# quadcopter.net
KiCad netlist of a schematic drawn in EAGLE
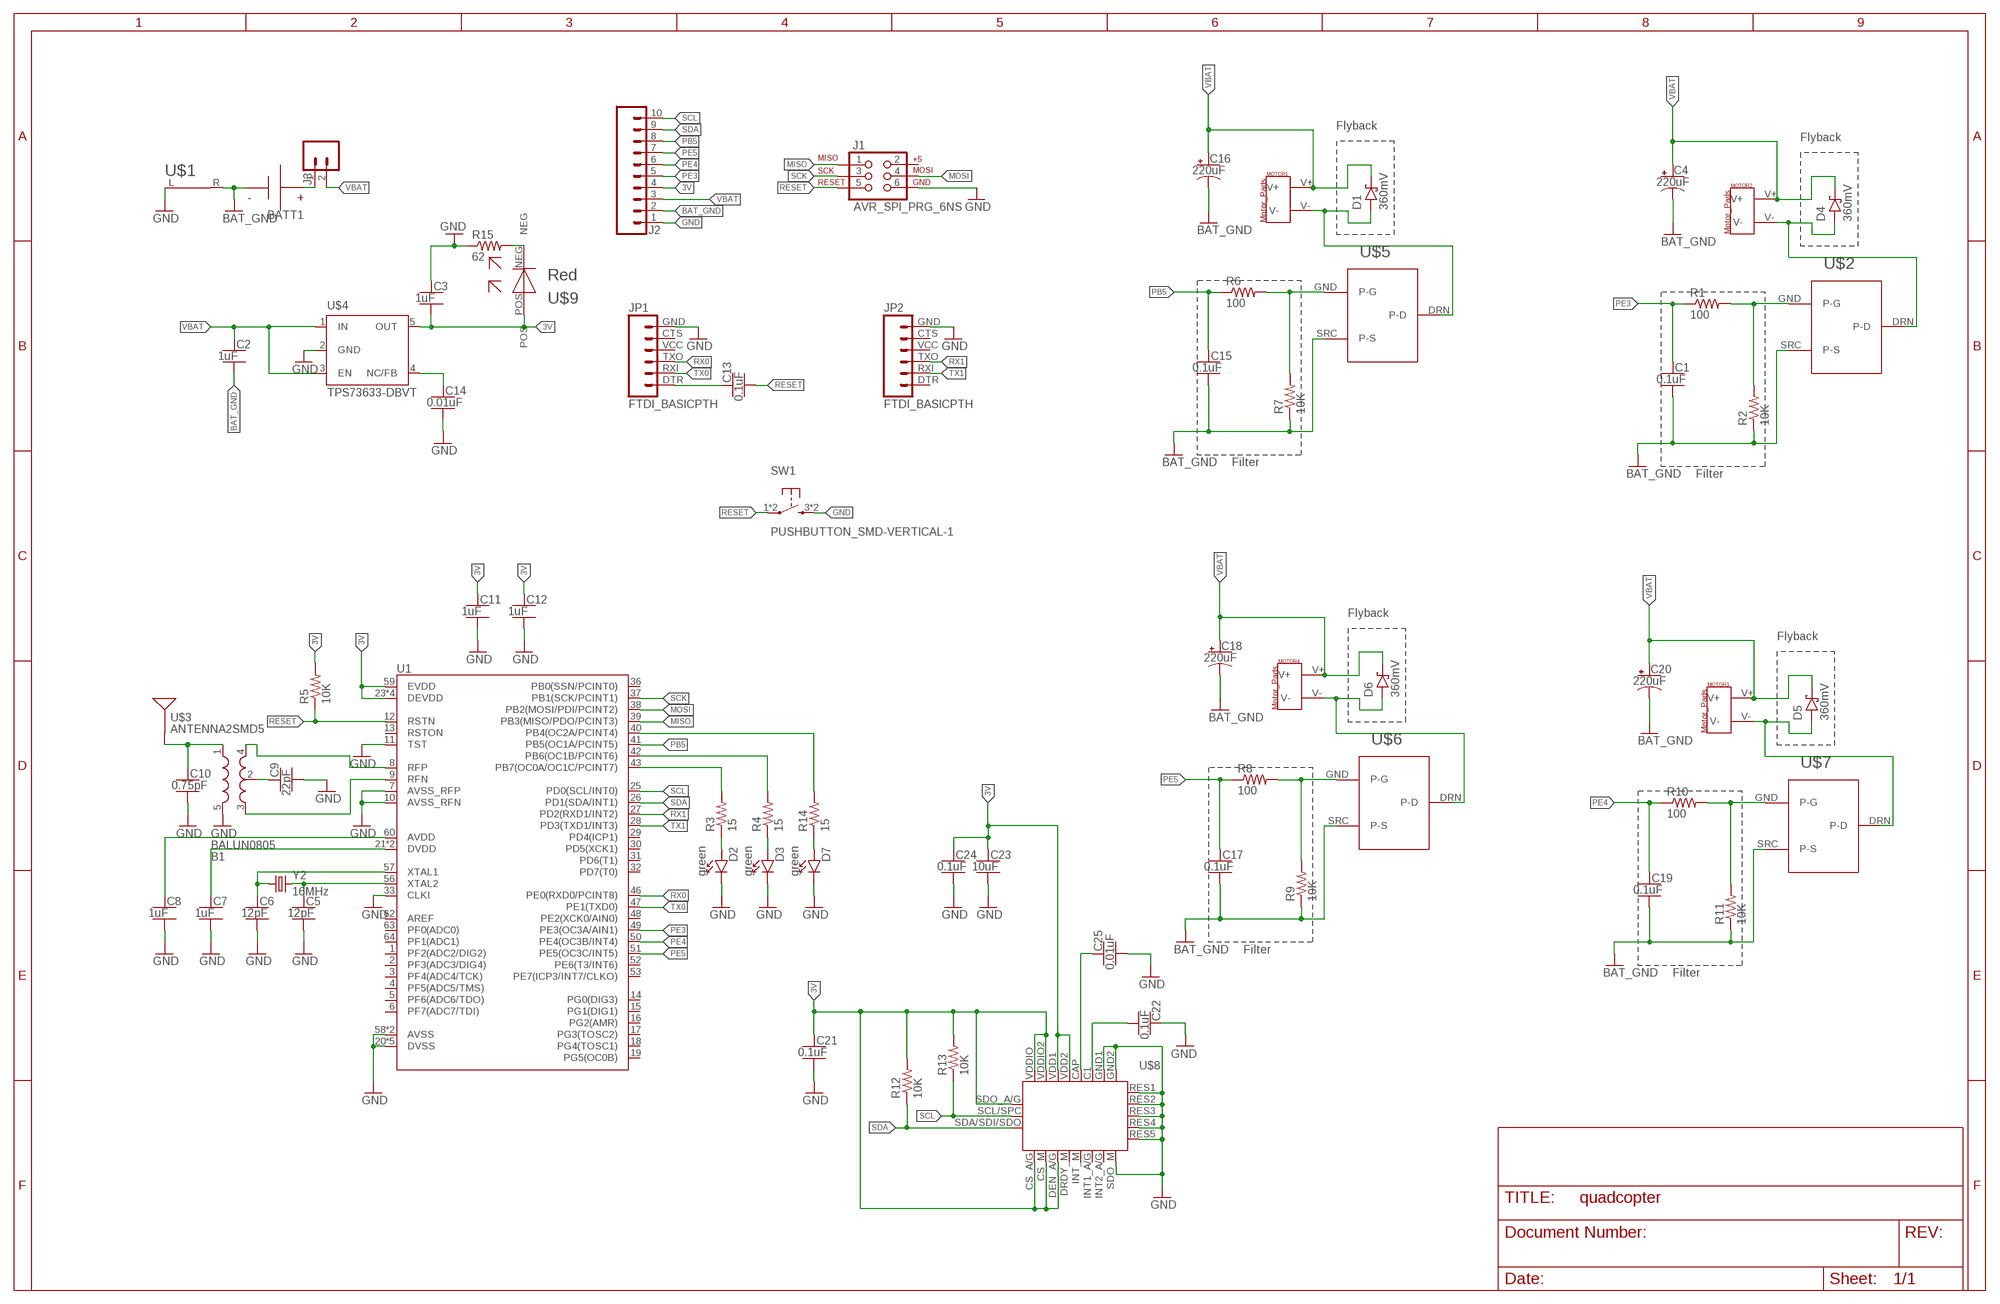
[diagram p0: schematic, sheet 1]

(export (version "E")
  (design (tool "Eeschema 10.0.6"))
  (components
    (comp (ref "B1")
      (value "BALUN0805")
      (footprint "eagle-import:BALUN")
      (fields (field (name "MFR") "Wurth Electronics Inc") (field (name "MPN") "748421245"))
      (libsource (lib "eagle-import") (part "BALUN0805"))
    )
    (comp (ref "BATT1")
      (value "BATTERY-HUBSAN-W/HOLDER")
      (footprint "eagle-import:BATTERY-W_HOLDER-380MAH-HUBSAN")
      (fields
        (field (name "MFR") "HUBSAN")
        (field (name "MPN") "X4-H107C-8-in-1")
        (field (name "CREATOR") "Swanson")
      )
      (libsource (lib "eagle-import") (part "BATTERY-HUBSAN-W/HOLDER"))
    )
    (comp (ref "C1")
      (value "0.1uF")
      (footprint "eagle-import:CAPC2012X140_HS")
      (fields
        (field (name "MFR") "Murata Electronics North America")
        (field (name "MPN") "GRM21BR71H104KA01L")
      )
      (libsource (lib "eagle-import") (part "CAPACITOR-NP_SMD-2012-0805_CERAMIC-0.1UF"))
    )
    (comp (ref "C2")
      (value "1uF")
      (footprint "eagle-import:CAPC2012X140_HS")
      (fields
        (field (name "MFR") "Murata Electronics North America")
        (field (name "MPN") "GRM21BR71H105KA12L")
      )
      (libsource (lib "eagle-import") (part "CAPACITOR-NP_SMD-2012-0805_CERAMIC-1UF"))
    )
    (comp (ref "C3")
      (value "1uF")
      (footprint "eagle-import:CAPC2012X140_HS")
      (fields
        (field (name "MFR") "Murata Electronics North America")
        (field (name "MPN") "GRM21BR71H105KA12L")
      )
      (libsource (lib "eagle-import") (part "CAPACITOR-NP_SMD-2012-0805_CERAMIC-1UF"))
    )
    (comp (ref "C4")
      (value "220uF")
      (footprint "eagle-import:CAPMP7343X310_HS")
      (fields (field (name "MFR") "AVX Corporation") (field (name "MPN") "TAJD227K006RNJ"))
      (libsource (lib "eagle-import") (part "CAPACITOR-POL_SMD-7043-D_TANTALUM-220UF"))
    )
    (comp (ref "C5")
      (value "12pF")
      (footprint "eagle-import:CAPC2012X140_HS")
      (fields
        (field (name "MFR") "Murata Electronics North America")
        (field (name "MPN") "GRM21A5C2E120JW01D")
      )
      (libsource (lib "eagle-import") (part "CAPACITOR-NP_SMD-2012-0805_CERAMIC-12PF"))
    )
    (comp (ref "C6")
      (value "12pF")
      (footprint "eagle-import:CAPC2012X140_HS")
      (fields
        (field (name "MFR") "Murata Electronics North America")
        (field (name "MPN") "GRM21A5C2E120JW01D")
      )
      (libsource (lib "eagle-import") (part "CAPACITOR-NP_SMD-2012-0805_CERAMIC-12PF"))
    )
    (comp (ref "C7")
      (value "1uF")
      (footprint "eagle-import:CAPC2012X140_HS")
      (fields
        (field (name "MFR") "Murata Electronics North America")
        (field (name "MPN") "GRM21BR71H105KA12L")
      )
      (libsource (lib "eagle-import") (part "CAPACITOR-NP_SMD-2012-0805_CERAMIC-1UF"))
    )
    (comp (ref "C8")
      (value "1uF")
      (footprint "eagle-import:CAPC2012X140_HS")
      (fields
        (field (name "MFR") "Murata Electronics North America")
        (field (name "MPN") "GRM21BR71H105KA12L")
      )
      (libsource (lib "eagle-import") (part "CAPACITOR-NP_SMD-2012-0805_CERAMIC-1UF"))
    )
    (comp (ref "C9")
      (value "22pF")
      (footprint "eagle-import:CAPC2012X140_HS")
      (fields
        (field (name "MFR") "Murata Electronics North America")
        (field (name "MPN") "GRM21A5C2E220JW01D")
      )
      (libsource (lib "eagle-import") (part "CAPACITOR-NP_SMD-2012-0805_CERAMIC-22PF"))
    )
    (comp (ref "C10")
      (value "0.75pF")
      (footprint "eagle-import:CAPC2012X140_HS")
      (fields
        (field (name "MFR") "Murata Electronics North America")
        (field (name "MPN") "GQM2195C2AR75CB01D")
      )
      (libsource (lib "eagle-import") (part "CAPACITOR-NP_SMD-2012-0805_CERAMIC-0.75PF"))
    )
    (comp (ref "C11")
      (value "1uF")
      (footprint "eagle-import:CAPC2012X140_HS")
      (fields
        (field (name "MFR") "Murata Electronics North America")
        (field (name "MPN") "GRM21BR71H105KA12L")
      )
      (libsource (lib "eagle-import") (part "CAPACITOR-NP_SMD-2012-0805_CERAMIC-1UF"))
    )
    (comp (ref "C12")
      (value "1uF")
      (footprint "eagle-import:CAPC2012X140_HS")
      (fields
        (field (name "MFR") "Murata Electronics North America")
        (field (name "MPN") "GRM21BR71H105KA12L")
      )
      (libsource (lib "eagle-import") (part "CAPACITOR-NP_SMD-2012-0805_CERAMIC-1UF"))
    )
    (comp (ref "C13")
      (value "0.1uF")
      (footprint "eagle-import:CAPC2012X140_HS")
      (fields
        (field (name "MFR") "Murata Electronics North America")
        (field (name "MPN") "GRM21BR71H104KA01L")
      )
      (libsource (lib "eagle-import") (part "CAPACITOR-NP_SMD-2012-0805_CERAMIC-0.1UF"))
    )
    (comp (ref "C14")
      (value "0.01uF")
      (footprint "eagle-import:CAPC2012X140_HS")
      (fields
        (field (name "MFR") "Murata Electronics North America")
        (field (name "MPN") "GRM2195C1H103FA01D")
      )
      (libsource (lib "eagle-import") (part "CAPACITOR-NP_SMD-2012-0805_CERAMIC-0.01UF"))
    )
    (comp (ref "C15")
      (value "0.1uF")
      (footprint "eagle-import:CAPC2012X140_HS")
      (fields
        (field (name "MFR") "Murata Electronics North America")
        (field (name "MPN") "GRM21BR71H104KA01L")
      )
      (libsource (lib "eagle-import") (part "CAPACITOR-NP_SMD-2012-0805_CERAMIC-0.1UF"))
    )
    (comp (ref "C16")
      (value "220uF")
      (footprint "eagle-import:CAPMP7343X310_HS")
      (fields (field (name "MFR") "AVX Corporation") (field (name "MPN") "TAJD227K006RNJ"))
      (libsource (lib "eagle-import") (part "CAPACITOR-POL_SMD-7043-D_TANTALUM-220UF"))
    )
    (comp (ref "C17")
      (value "0.1uF")
      (footprint "eagle-import:CAPC2012X140_HS")
      (fields
        (field (name "MFR") "Murata Electronics North America")
        (field (name "MPN") "GRM21BR71H104KA01L")
      )
      (libsource (lib "eagle-import") (part "CAPACITOR-NP_SMD-2012-0805_CERAMIC-0.1UF"))
    )
    (comp (ref "C18")
      (value "220uF")
      (footprint "eagle-import:CAPMP7343X310_HS")
      (fields (field (name "MFR") "AVX Corporation") (field (name "MPN") "TAJD227K006RNJ"))
      (libsource (lib "eagle-import") (part "CAPACITOR-POL_SMD-7043-D_TANTALUM-220UF"))
    )
    (comp (ref "C19")
      (value "0.1uF")
      (footprint "eagle-import:CAPC2012X140_HS")
      (fields
        (field (name "MFR") "Murata Electronics North America")
        (field (name "MPN") "GRM21BR71H104KA01L")
      )
      (libsource (lib "eagle-import") (part "CAPACITOR-NP_SMD-2012-0805_CERAMIC-0.1UF"))
    )
    (comp (ref "C20")
      (value "220uF")
      (footprint "eagle-import:CAPMP7343X310_HS")
      (fields (field (name "MFR") "AVX Corporation") (field (name "MPN") "TAJD227K006RNJ"))
      (libsource (lib "eagle-import") (part "CAPACITOR-POL_SMD-7043-D_TANTALUM-220UF"))
    )
    (comp (ref "C21")
      (value "0.1uF")
      (footprint "eagle-import:CAPC2012X140_HS")
      (fields
        (field (name "MFR") "Murata Electronics North America")
        (field (name "MPN") "GRM21BR71H104KA01L")
      )
      (libsource (lib "eagle-import") (part "CAPACITOR-NP_SMD-2012-0805_CERAMIC-0.1UF"))
    )
    (comp (ref "C22")
      (value "0.1uF")
      (footprint "eagle-import:CAPC2012X140_HS")
      (fields
        (field (name "MFR") "Murata Electronics North America")
        (field (name "MPN") "GRM21BR71H104KA01L")
      )
      (libsource (lib "eagle-import") (part "CAPACITOR-NP_SMD-2012-0805_CERAMIC-0.1UF"))
    )
    (comp (ref "C23")
      (value "10uF")
      (footprint "eagle-import:CAPC2012X140_HS")
      (fields
        (field (name "MFR") "Murata Electronics North America")
        (field (name "MPN") "GRM21BR61E106KA73L")
      )
      (libsource (lib "eagle-import") (part "CAPACITOR-NP_SMD-2012-0805_CERAMIC-10UF"))
    )
    (comp (ref "C24")
      (value "0.1uF")
      (footprint "eagle-import:CAPC2012X140_HS")
      (fields
        (field (name "MFR") "Murata Electronics North America")
        (field (name "MPN") "GRM21BR71H104KA01L")
      )
      (libsource (lib "eagle-import") (part "CAPACITOR-NP_SMD-2012-0805_CERAMIC-0.1UF"))
    )
    (comp (ref "C25")
      (value "0.01uF")
      (footprint "eagle-import:CAPC2012X140_HS")
      (fields
        (field (name "MFR") "Murata Electronics North America")
        (field (name "MPN") "GRM2195C1H103FA01D")
      )
      (libsource (lib "eagle-import") (part "CAPACITOR-NP_SMD-2012-0805_CERAMIC-0.01UF"))
    )
    (comp (ref "D1")
      (value "360mV")
      (footprint "eagle-import:SOD3716X135_HS")
      (fields
        (field (name "MFR") "Toshiba Semiconductor and Storage")
        (field (name "MPN") "CRS08(TE85L,Q,M)")
      )
      (libsource (lib "eagle-import") (part "DIODE-SCHOTTKY_SMD-SOD123-360MV"))
    )
    (comp (ref "D2")
      (value "green")
      (footprint "eagle-import:LEDSC125X200X120-2_HS")
      (fields (field (name "MFR") "Lite-On Inc") (field (name "MPN") "LTST-C170GKT"))
      (libsource (lib "eagle-import") (part "DIODE-LED_SMD-2012-0805-GREEN"))
    )
    (comp (ref "D3")
      (value "green")
      (footprint "eagle-import:LEDSC125X200X120-2_HS")
      (fields (field (name "MFR") "Lite-On Inc") (field (name "MPN") "LTST-C170GKT"))
      (libsource (lib "eagle-import") (part "DIODE-LED_SMD-2012-0805-GREEN"))
    )
    (comp (ref "D4")
      (value "360mV")
      (footprint "eagle-import:SOD3716X135_HS")
      (fields
        (field (name "MFR") "Toshiba Semiconductor and Storage")
        (field (name "MPN") "CRS08(TE85L,Q,M)")
      )
      (libsource (lib "eagle-import") (part "DIODE-SCHOTTKY_SMD-SOD123-360MV"))
    )
    (comp (ref "D5")
      (value "360mV")
      (footprint "eagle-import:SOD3716X135_HS")
      (fields
        (field (name "MFR") "Toshiba Semiconductor and Storage")
        (field (name "MPN") "CRS08(TE85L,Q,M)")
      )
      (libsource (lib "eagle-import") (part "DIODE-SCHOTTKY_SMD-SOD123-360MV"))
    )
    (comp (ref "D6")
      (value "360mV")
      (footprint "eagle-import:SOD3716X135_HS")
      (fields
        (field (name "MFR") "Toshiba Semiconductor and Storage")
        (field (name "MPN") "CRS08(TE85L,Q,M)")
      )
      (libsource (lib "eagle-import") (part "DIODE-SCHOTTKY_SMD-SOD123-360MV"))
    )
    (comp (ref "D7")
      (value "green")
      (footprint "eagle-import:LEDSC125X200X120-2_HS")
      (fields (field (name "MFR") "Lite-On Inc") (field (name "MPN") "LTST-C170GKT"))
      (libsource (lib "eagle-import") (part "DIODE-LED_SMD-2012-0805-GREEN"))
    )
    (comp (ref "J1")
      (value "AVR_SPI_PRG_6NS")
      (footprint "eagle-import:2X3-NS")
      (fields (field (name "MFR") "Amphenol FCI") (field (name "MPN") "67997-206HLF"))
      (libsource (lib "eagle-import") (part "AVR_SPI_PRG_6NS"))
    )
    (comp (ref "J2")
      (value "SIP-10_TH-254X10")
      (footprint "eagle-import:HDRV10W63P254_10X1_2540X254H838_HS")
      (fields (field (name "MFR") "Amphenol FCI") (field (name "MPN") "68000-110HLF"))
      (libsource (lib "eagle-import") (part "SIP-10_TH-254X10"))
    )
    (comp (ref "J3")
      (value "MALE_HEADER_2POS-2X1-0.1IN")
      (footprint "eagle-import:MALE_HEADER_2X1_0.1IN")
      (fields
        (field (name "MFR") "3M")
        (field (name "MPN") "961102-6404-AR")
        (field (name "CREATOR") "SWANSON")
        (field (name "REVIEWER") "John Wu")
      )
      (libsource (lib "eagle-import") (part "MALE_HEADER_2POS-2X1-0.1IN"))
    )
    (comp (ref "JP1")
      (value "FTDI_BASICPTH")
      (footprint "eagle-import:FTDI_BASIC")
      (fields (field (name "MFR") "Amphenol FCI") (field (name "MPN") "68016-406HLF"))
      (libsource (lib "eagle-import") (part "FTDI_BASICPTH"))
    )
    (comp (ref "JP2")
      (value "FTDI_BASICPTH")
      (footprint "eagle-import:FTDI_BASIC")
      (fields (field (name "MFR") "Amphenol FCI") (field (name "MPN") "68016-406HLF"))
      (libsource (lib "eagle-import") (part "FTDI_BASICPTH"))
    )
    (comp (ref "MOTOR1")
      (value "MOTOR_PADS")
      (footprint "eagle-import:MOTOR_PADS")
      (fields (field (name "MFR") "NA"))
      (libsource (lib "eagle-import") (part "MOTOR_PADS"))
    )
    (comp (ref "MOTOR2")
      (value "MOTOR_PADS")
      (footprint "eagle-import:MOTOR_PADS")
      (fields (field (name "MFR") "NA"))
      (libsource (lib "eagle-import") (part "MOTOR_PADS"))
    )
    (comp (ref "MOTOR3")
      (value "MOTOR_PADS")
      (footprint "eagle-import:MOTOR_PADS")
      (fields (field (name "MFR") "NA"))
      (libsource (lib "eagle-import") (part "MOTOR_PADS"))
    )
    (comp (ref "MOTOR4")
      (value "MOTOR_PADS")
      (footprint "eagle-import:MOTOR_PADS")
      (fields (field (name "MFR") "NA"))
      (libsource (lib "eagle-import") (part "MOTOR_PADS"))
    )
    (comp (ref "R1")
      (value "100")
      (footprint "eagle-import:RESC2012X60_HS")
      (fields (field (name "MFR") "Yageo") (field (name "MPN") "RC0805JR-07100RL"))
      (libsource (lib "eagle-import") (part "RESISTOR_SMD-2012-0805-100"))
    )
    (comp (ref "R2")
      (value "10K")
      (footprint "eagle-import:RESC2012X60_HS")
      (fields (field (name "MFR") "Yageo") (field (name "MPN") "RC0805JR-0710KL"))
      (libsource (lib "eagle-import") (part "RESISTOR_SMD-2012-0805-10K"))
    )
    (comp (ref "R3")
      (value "15")
      (footprint "eagle-import:RESC2012X60_HS")
      (fields
        (field (name "MFR") "Yageo")
        (field (name "MPN") "RC0805JR-0715RL")
        (field (name "CREATOR") "Joshua Crook")
        (field (name "REVIEWER") "John Wu")
      )
      (libsource (lib "eagle-import") (part "RESISTOR_SMD-2012-0805-15"))
    )
    (comp (ref "R4")
      (value "15")
      (footprint "eagle-import:RESC2012X60_HS")
      (fields
        (field (name "MFR") "Yageo")
        (field (name "MPN") "RC0805JR-0715RL")
        (field (name "CREATOR") "Joshua Crook")
        (field (name "REVIEWER") "John Wu")
      )
      (libsource (lib "eagle-import") (part "RESISTOR_SMD-2012-0805-15"))
    )
    (comp (ref "R5")
      (value "10K")
      (footprint "eagle-import:RESC2012X60_HS")
      (fields (field (name "MFR") "Yageo") (field (name "MPN") "RC0805JR-0710KL"))
      (libsource (lib "eagle-import") (part "RESISTOR_SMD-2012-0805-10K"))
    )
    (comp (ref "R6")
      (value "100")
      (footprint "eagle-import:RESC2012X60_HS")
      (fields (field (name "MFR") "Yageo") (field (name "MPN") "RC0805JR-07100RL"))
      (libsource (lib "eagle-import") (part "RESISTOR_SMD-2012-0805-100"))
    )
    (comp (ref "R7")
      (value "10K")
      (footprint "eagle-import:RESC2012X60_HS")
      (fields (field (name "MFR") "Yageo") (field (name "MPN") "RC0805JR-0710KL"))
      (libsource (lib "eagle-import") (part "RESISTOR_SMD-2012-0805-10K"))
    )
    (comp (ref "R8")
      (value "100")
      (footprint "eagle-import:RESC2012X60_HS")
      (fields (field (name "MFR") "Yageo") (field (name "MPN") "RC0805JR-07100RL"))
      (libsource (lib "eagle-import") (part "RESISTOR_SMD-2012-0805-100"))
    )
    (comp (ref "R9")
      (value "10K")
      (footprint "eagle-import:RESC2012X60_HS")
      (fields (field (name "MFR") "Yageo") (field (name "MPN") "RC0805JR-0710KL"))
      (libsource (lib "eagle-import") (part "RESISTOR_SMD-2012-0805-10K"))
    )
    (comp (ref "R10")
      (value "100")
      (footprint "eagle-import:RESC2012X60_HS")
      (fields (field (name "MFR") "Yageo") (field (name "MPN") "RC0805JR-07100RL"))
      (libsource (lib "eagle-import") (part "RESISTOR_SMD-2012-0805-100"))
    )
    (comp (ref "R11")
      (value "10K")
      (footprint "eagle-import:RESC2012X60_HS")
      (fields (field (name "MFR") "Yageo") (field (name "MPN") "RC0805JR-0710KL"))
      (libsource (lib "eagle-import") (part "RESISTOR_SMD-2012-0805-10K"))
    )
    (comp (ref "R12")
      (value "10K")
      (footprint "eagle-import:RESC2012X60_HS")
      (fields (field (name "MFR") "Yageo") (field (name "MPN") "RC0805JR-0710KL"))
      (libsource (lib "eagle-import") (part "RESISTOR_SMD-2012-0805-10K"))
    )
    (comp (ref "R13")
      (value "10K")
      (footprint "eagle-import:RESC2012X60_HS")
      (fields (field (name "MFR") "Yageo") (field (name "MPN") "RC0805JR-0710KL"))
      (libsource (lib "eagle-import") (part "RESISTOR_SMD-2012-0805-10K"))
    )
    (comp (ref "R14")
      (value "15")
      (footprint "eagle-import:RESC2012X60_HS")
      (fields
        (field (name "MFR") "Yageo")
        (field (name "MPN") "RC0805JR-0715RL")
        (field (name "CREATOR") "Joshua Crook")
        (field (name "REVIEWER") "John Wu")
      )
      (libsource (lib "eagle-import") (part "RESISTOR_SMD-2012-0805-15"))
    )
    (comp (ref "R15")
      (value "62")
      (footprint "eagle-import:RESC2012X60_HS")
      (fields
        (field (name "MFR") "Yageo")
        (field (name "MPN") "RC0805JR-0762RL")
        (field (name "CREATOR") "Joshua Crook")
        (field (name "REVIEWER") "John Wu")
      )
      (libsource (lib "eagle-import") (part "RESISTOR_SMD-2012-0805-62"))
    )
    (comp (ref "SW1")
      (value "PUSHBUTTON_SMD-VERTICAL-1")
      (footprint "eagle-import:TE_FSM8JSMA_HS")
      (fields (field (name "MFR") "TE Connectivity Alcoswitch Switches") (field (name "MPN") "FSM4JSMA"))
      (libsource (lib "eagle-import") (part "PUSHBUTTON_SMD-VERTICAL-1"))
    )
    (comp (ref "U$1")
      (value "NET_BRIDGE")
      (footprint "eagle-import:NET_BRIDGE")
      (fields (field (name "CREATOR") "Joshua Crook") (field (name "REVIEWER") "John Wu"))
      (libsource (lib "eagle-import") (part "NET_BRIDGE"))
    )
    (comp (ref "U$2")
      (value "MOSFET_20V")
      (footprint "eagle-import:MOSFET_20V")
      (fields
        (field (name "MFR") "Vishay Siliconix")
        (field (name "MPN") "SI2302CDS-T1-E3")
        (field (name "CREATOR") "Alexander Orr")
        (field (name "REVIEWER") "John Wu")
      )
      (libsource (lib "eagle-import") (part "MOSFET_20V"))
    )
    (comp (ref "U$3")
      (value "ANTENNA2SMD5")
      (footprint "eagle-import:ANTENNA-CHIP5")
      (fields (field (name "MFR") "Linx Technologies Inc.") (field (name "MPN") "ANT-2.45-CHP-T"))
      (libsource (lib "eagle-import") (part "ANTENNA2SMD5"))
    )
    (comp (ref "U$4")
      (value "TPS73633-DBVT")
      (footprint "eagle-import:SOT23-DBV")
      (fields (field (name "MFR") "Texas Instruments") (field (name "MPN") "LP3985IM5X-3.0/NOPB"))
      (libsource (lib "eagle-import") (part "TPS73633-DBVT"))
    )
    (comp (ref "U$5")
      (value "MOSFET_20V")
      (footprint "eagle-import:MOSFET_20V")
      (fields
        (field (name "MFR") "Vishay Siliconix")
        (field (name "MPN") "SI2302CDS-T1-E3")
        (field (name "CREATOR") "Alexander Orr")
        (field (name "REVIEWER") "John Wu")
      )
      (libsource (lib "eagle-import") (part "MOSFET_20V"))
    )
    (comp (ref "U$6")
      (value "MOSFET_20V")
      (footprint "eagle-import:MOSFET_20V")
      (fields
        (field (name "MFR") "Vishay Siliconix")
        (field (name "MPN") "SI2302CDS-T1-E3")
        (field (name "CREATOR") "Alexander Orr")
        (field (name "REVIEWER") "John Wu")
      )
      (libsource (lib "eagle-import") (part "MOSFET_20V"))
    )
    (comp (ref "U$7")
      (value "MOSFET_20V")
      (footprint "eagle-import:MOSFET_20V")
      (fields
        (field (name "MFR") "Vishay Siliconix")
        (field (name "MPN") "SI2302CDS-T1-E3")
        (field (name "CREATOR") "Alexander Orr")
        (field (name "REVIEWER") "John Wu")
      )
      (libsource (lib "eagle-import") (part "MOSFET_20V"))
    )
    (comp (ref "U$8")
      (value "IMU_9AXIS")
      (footprint "eagle-import:IMU_9AXIS")
      (fields
        (field (name "MFR") "STMicroelectronics")
        (field (name "MPN") "LSM9DS1TR")
        (field (name "CREATOR") "Alex Orr")
        (field (name "REVIEWER") "John Wu")
      )
      (libsource (lib "eagle-import") (part "IMU_9AXIS"))
    )
    (comp (ref "U$9")
      (value "Red")
      (footprint "eagle-import:RED_LED_0805")
      (fields
        (field (name "MFR") "OSRAM Opto Semiconductors Inc.")
        (field (name "MPN") "LS R976-NR-1")
        (field (name "CREATOR") "Alexander Orr")
        (field (name "REVIEWER") "John Wu")
      )
      (libsource (lib "eagle-import") (part "RED_LED_0805"))
    )
    (comp (ref "U1")
      (value "ATMEGA128RFA1")
      (footprint "eagle-import:QFN-64")
      (fields
        (field (name "MFR") "Atmel")
        (field (name "MPN") "ATMEGA128RFA1-ZUR00")
        (field (name "CREATOR") "Swanson")
      )
      (libsource (lib "eagle-import") (part "ATMEGA128RFA1"))
    )
    (comp (ref "Y2")
      (value "16MHz")
      (footprint "eagle-import:CRYSTAL-SMD-5X3")
      (fields (field (name "MFR") "Abracon LLC") (field (name "MPN") "ABM3B-16.000MHZ-B2-T"))
      (libsource (lib "eagle-import") (part "CRYSTAL5X3"))
    )
  )
  (nets
    (net (code "1") (name "3V") (class "Default")
      (node (ref "C11") (pin "1") (pinfunction "1_1") (pintype "passive"))
      (node (ref "C12") (pin "1") (pinfunction "1_1") (pintype "passive"))
      (node (ref "C21") (pin "1") (pinfunction "1_1") (pintype "passive"))
      (node (ref "C23") (pin "1") (pinfunction "1_1") (pintype "passive"))
      (node (ref "C24") (pin "1") (pinfunction "1_1") (pintype "passive"))
      (node (ref "C3") (pin "2") (pinfunction "2_2") (pintype "passive"))
      (node (ref "J2") (pin "4") (pinfunction "4_4") (pintype "passive"))
      (node (ref "R12") (pin "2") (pinfunction "2_2") (pintype "passive"))
      (node (ref "R13") (pin "2") (pinfunction "2_2") (pintype "passive"))
      (node (ref "R5") (pin "2") (pinfunction "2_2") (pintype "passive"))
      (node (ref "U$4") (pin "5") (pinfunction "OUT_5") (pintype "passive"))
      (node (ref "U$8") (pin "CS_A/G") (pinfunction "CS_A/G_CS_A/G") (pintype "bidirectional"))
      (node (ref "U$8") (pin "CS_M") (pinfunction "CS_M_CS_M") (pintype "bidirectional"))
      (node (ref "U$8") (pin "DEN_A/G") (pinfunction "DEN_A/G_DEN_A/G") (pintype "bidirectional"))
      (node (ref "U$8") (pin "SDO_A/G") (pinfunction "SDO_A/G_SDO_A/G") (pintype "bidirectional"))
      (node (ref "U$8") (pin "VDD1") (pinfunction "VDD1_VDD1") (pintype "bidirectional"))
      (node (ref "U$8") (pin "VDD2") (pinfunction "VDD2_VDD2") (pintype "bidirectional"))
      (node (ref "U$8") (pin "VDDIO") (pinfunction "VDDIO1_VDDIO") (pintype "bidirectional"))
      (node (ref "U$8") (pin "VDDIO2") (pinfunction "VDDIO2_VDDIO2") (pintype "bidirectional"))
      (node (ref "U$9") (pin "POS") (pinfunction "POS_POS") (pintype "passive"))
      (node (ref "U1") (pin "23") (pinfunction "DEVDD_23") (pintype "bidirectional"))
      (node (ref "U1") (pin "34") (pinfunction "DEVDD_34") (pintype "bidirectional"))
      (node (ref "U1") (pin "44") (pinfunction "DEVDD_44") (pintype "bidirectional"))
      (node (ref "U1") (pin "54") (pinfunction "DEVDD_54") (pintype "bidirectional"))
      (node (ref "U1") (pin "59") (pinfunction "EVDD_59") (pintype "bidirectional"))
    )
    (net (code "2") (name "BAT_GND") (class "Default")
      (node (ref "BATT1") (pin "-") (pinfunction "N_-") (pintype "bidirectional"))
      (node (ref "C1") (pin "2") (pinfunction "2_2") (pintype "passive"))
      (node (ref "C15") (pin "2") (pinfunction "2_2") (pintype "passive"))
      (node (ref "C16") (pin "2") (pinfunction "-_2") (pintype "passive"))
      (node (ref "C17") (pin "2") (pinfunction "2_2") (pintype "passive"))
      (node (ref "C18") (pin "2") (pinfunction "-_2") (pintype "passive"))
      (node (ref "C19") (pin "2") (pinfunction "2_2") (pintype "passive"))
      (node (ref "C2") (pin "2") (pinfunction "2_2") (pintype "passive"))
      (node (ref "C20") (pin "2") (pinfunction "-_2") (pintype "passive"))
      (node (ref "C4") (pin "2") (pinfunction "-_2") (pintype "passive"))
      (node (ref "J2") (pin "2") (pinfunction "2_2") (pintype "passive"))
      (node (ref "R11") (pin "1") (pinfunction "1_1") (pintype "passive"))
      (node (ref "R2") (pin "1") (pinfunction "1_1") (pintype "passive"))
      (node (ref "R7") (pin "1") (pinfunction "1_1") (pintype "passive"))
      (node (ref "R9") (pin "1") (pinfunction "1_1") (pintype "passive"))
      (node (ref "U$1") (pin "R") (pinfunction "R_R") (pintype "passive"))
      (node (ref "U$2") (pin "SRC") (pinfunction "P-S_SRC") (pintype "passive"))
      (node (ref "U$5") (pin "SRC") (pinfunction "P-S_SRC") (pintype "passive"))
      (node (ref "U$6") (pin "SRC") (pinfunction "P-S_SRC") (pintype "passive"))
      (node (ref "U$7") (pin "SRC") (pinfunction "P-S_SRC") (pintype "passive"))
    )
    (net (code "3") (name "GND") (class "Default")
      (node (ref "B1") (pin "5") (pinfunction "GND_5") (pintype "bidirectional"))
      (node (ref "C10") (pin "2") (pinfunction "2_2") (pintype "passive"))
      (node (ref "C11") (pin "2") (pinfunction "2_2") (pintype "passive"))
      (node (ref "C12") (pin "2") (pinfunction "2_2") (pintype "passive"))
      (node (ref "C14") (pin "2") (pinfunction "2_2") (pintype "passive"))
      (node (ref "C21") (pin "2") (pinfunction "2_2") (pintype "passive"))
      (node (ref "C22") (pin "1") (pinfunction "1_1") (pintype "passive"))
      (node (ref "C23") (pin "2") (pinfunction "2_2") (pintype "passive"))
      (node (ref "C24") (pin "2") (pinfunction "2_2") (pintype "passive"))
      (node (ref "C25") (pin "2") (pinfunction "2_2") (pintype "passive"))
      (node (ref "C3") (pin "1") (pinfunction "1_1") (pintype "passive"))
      (node (ref "C5") (pin "2") (pinfunction "2_2") (pintype "passive"))
      (node (ref "C6") (pin "2") (pinfunction "2_2") (pintype "passive"))
      (node (ref "C7") (pin "2") (pinfunction "2_2") (pintype "passive"))
      (node (ref "C8") (pin "2") (pinfunction "2_2") (pintype "passive"))
      (node (ref "C9") (pin "2") (pinfunction "2_2") (pintype "passive"))
      (node (ref "D2") (pin "C") (pinfunction "C_C") (pintype "passive"))
      (node (ref "D3") (pin "C") (pinfunction "C_C") (pintype "passive"))
      (node (ref "D7") (pin "C") (pinfunction "C_C") (pintype "passive"))
      (node (ref "J1") (pin "6") (pinfunction "6_6") (pintype "passive"))
      (node (ref "J2") (pin "1") (pinfunction "1_1") (pintype "passive"))
      (node (ref "JP1") (pin "GND") (pinfunction "6_GND") (pintype "passive"))
      (node (ref "JP2") (pin "GND") (pinfunction "6_GND") (pintype "passive"))
      (node (ref "R15") (pin "1") (pinfunction "1_1") (pintype "passive"))
      (node (ref "SW1") (pin "3") (pinfunction "2_3") (pintype "passive"))
      (node (ref "SW1") (pin "4") (pinfunction "2_4") (pintype "passive"))
      (node (ref "U$1") (pin "L") (pinfunction "L_L") (pintype "passive"))
      (node (ref "U$4") (pin "2") (pinfunction "GND_2") (pintype "input"))
      (node (ref "U$8") (pin "GND1") (pinfunction "GND1_GND1") (pintype "bidirectional"))
      (node (ref "U$8") (pin "GND2") (pinfunction "GND2_GND2") (pintype "bidirectional"))
      (node (ref "U$8") (pin "RES1") (pinfunction "RES1_RES1") (pintype "bidirectional"))
      (node (ref "U$8") (pin "RES2") (pinfunction "RES2_RES2") (pintype "bidirectional"))
      (node (ref "U$8") (pin "RES3") (pinfunction "RES3_RES3") (pintype "bidirectional"))
      (node (ref "U$8") (pin "RES4") (pinfunction "RES4_RES4") (pintype "bidirectional"))
      (node (ref "U$8") (pin "RES5") (pinfunction "RES5_RES5") (pintype "bidirectional"))
      (node (ref "U$8") (pin "SDO_M") (pinfunction "SDO_M_SDO_M") (pintype "bidirectional"))
      (node (ref "U1") (pin "10") (pinfunction "AVSS_RFN_10") (pintype "bidirectional"))
      (node (ref "U1") (pin "11") (pinfunction "TST_11") (pintype "bidirectional"))
      (node (ref "U1") (pin "20") (pinfunction "DVSS_20") (pintype "bidirectional"))
      (node (ref "U1") (pin "24") (pinfunction "DVSS_24") (pintype "bidirectional"))
      (node (ref "U1") (pin "33") (pinfunction "CLKI_33") (pintype "bidirectional"))
      (node (ref "U1") (pin "35") (pinfunction "DVSS_35") (pintype "bidirectional"))
      (node (ref "U1") (pin "45") (pinfunction "DVSS_45") (pintype "bidirectional"))
      (node (ref "U1") (pin "55") (pinfunction "DVSS_55") (pintype "bidirectional"))
      (node (ref "U1") (pin "58") (pinfunction "AVSS_58") (pintype "bidirectional"))
      (node (ref "U1") (pin "61") (pinfunction "AVSS_61") (pintype "bidirectional"))
      (node (ref "U1") (pin "7") (pinfunction "AVSS_RFP_7") (pintype "bidirectional"))
    )
    (net (code "4") (name "MISO") (class "Default")
      (node (ref "J1") (pin "1") (pinfunction "1_1") (pintype "passive"))
      (node (ref "U1") (pin "39") (pinfunction "PB3(MISO/PDO/PCINT3)_39") (pintype "bidirectional"))
    )
    (net (code "5") (name "MOSI") (class "Default")
      (node (ref "J1") (pin "4") (pinfunction "4_4") (pintype "passive"))
      (node (ref "U1") (pin "38") (pinfunction "PB2(MOSI/PDI/PCINT2)_38") (pintype "bidirectional"))
    )
    (net (code "6") (name "Net-(B1-GND-Pad2)") (class "Default")
      (node (ref "B1") (pin "2") (pinfunction "GND_2") (pintype "bidirectional"))
      (node (ref "C9") (pin "1") (pinfunction "1_1") (pintype "passive"))
    )
    (net (code "7") (name "Net-(B1-IN)") (class "Default")
      (node (ref "B1") (pin "1") (pinfunction "IN_1") (pintype "bidirectional"))
      (node (ref "C10") (pin "1") (pinfunction "1_1") (pintype "passive"))
      (node (ref "U$3") (pin "FEED") (pinfunction "SIGNAL_FEED") (pintype "bidirectional"))
    )
    (net (code "8") (name "Net-(B1-OUT1)") (class "Default")
      (node (ref "B1") (pin "4") (pinfunction "OUT1_4") (pintype "bidirectional"))
      (node (ref "U1") (pin "8") (pinfunction "RFP_8") (pintype "bidirectional"))
    )
    (net (code "9") (name "Net-(B1-OUT2)") (class "Default")
      (node (ref "B1") (pin "3") (pinfunction "OUT2_3") (pintype "bidirectional"))
      (node (ref "U1") (pin "9") (pinfunction "RFN_9") (pintype "bidirectional"))
    )
    (net (code "10") (name "Net-(BATT1-P)") (class "Default")
      (node (ref "BATT1") (pin "+") (pinfunction "P_+") (pintype "bidirectional"))
      (node (ref "J3") (pin "1") (pinfunction "1_1") (pintype "passive"))
    )
    (net (code "11") (name "Net-(C7-Pad1)") (class "Default")
      (node (ref "C7") (pin "1") (pinfunction "1_1") (pintype "passive"))
      (node (ref "U1") (pin "21") (pinfunction "DVDD_21") (pintype "bidirectional"))
      (node (ref "U1") (pin "22") (pinfunction "DVDD_22") (pintype "bidirectional"))
    )
    (net (code "12") (name "Net-(C22-Pad2)") (class "Default")
      (node (ref "C22") (pin "2") (pinfunction "2_2") (pintype "passive"))
      (node (ref "U$8") (pin "C1") (pinfunction "C1_C1") (pintype "bidirectional"))
    )
    (net (code "13") (name "Net-(C25-Pad1)") (class "Default")
      (node (ref "C25") (pin "1") (pinfunction "1_1") (pintype "passive"))
      (node (ref "U$8") (pin "CAP") (pinfunction "CAP_CAP") (pintype "bidirectional"))
    )
    (net (code "14") (name "Net-(D2-PadA)") (class "Default")
      (node (ref "D2") (pin "A") (pinfunction "A_A") (pintype "passive"))
      (node (ref "R3") (pin "1") (pinfunction "1_1") (pintype "passive"))
    )
    (net (code "15") (name "Net-(D3-PadA)") (class "Default")
      (node (ref "D3") (pin "A") (pinfunction "A_A") (pintype "passive"))
      (node (ref "R4") (pin "1") (pinfunction "1_1") (pintype "passive"))
    )
    (net (code "16") (name "Net-(D7-PadA)") (class "Default")
      (node (ref "D7") (pin "A") (pinfunction "A_A") (pintype "passive"))
      (node (ref "R14") (pin "1") (pinfunction "1_1") (pintype "passive"))
    )
    (net (code "17") (name "Net-(JP1-1)") (class "Default")
      (node (ref "C13") (pin "1") (pinfunction "1_1") (pintype "passive"))
      (node (ref "JP1") (pin "DTR") (pinfunction "1_DTR") (pintype "passive"))
    )
    (net (code "18") (name "Net-(R15-Pad2)") (class "Default")
      (node (ref "R15") (pin "2") (pinfunction "2_2") (pintype "passive"))
      (node (ref "U$9") (pin "NEG") (pinfunction "NEG_NEG") (pintype "passive"))
    )
    (net (code "19") (name "Net-(U$2-P-D)") (class "Default")
      (node (ref "D4") (pin "A") (pinfunction "A_A") (pintype "passive"))
      (node (ref "MOTOR2") (pin "V-") (pinfunction "V-_V-") (pintype "bidirectional"))
      (node (ref "U$2") (pin "DRN") (pinfunction "P-D_DRN") (pintype "passive"))
    )
    (net (code "20") (name "Net-(U$2-P-G)") (class "Default")
      (node (ref "R1") (pin "2") (pinfunction "2_2") (pintype "passive"))
      (node (ref "R2") (pin "2") (pinfunction "2_2") (pintype "passive"))
      (node (ref "U$2") (pin "GND") (pinfunction "P-G_GND") (pintype "passive"))
    )
    (net (code "21") (name "Net-(U$4-NC{slash}FB)") (class "Default")
      (node (ref "C14") (pin "1") (pinfunction "1_1") (pintype "passive"))
      (node (ref "U$4") (pin "4") (pinfunction "NC/FB_4") (pintype "passive"))
    )
    (net (code "22") (name "Net-(U$5-P-D)") (class "Default")
      (node (ref "D1") (pin "A") (pinfunction "A_A") (pintype "passive"))
      (node (ref "MOTOR1") (pin "V-") (pinfunction "V-_V-") (pintype "bidirectional"))
      (node (ref "U$5") (pin "DRN") (pinfunction "P-D_DRN") (pintype "passive"))
    )
    (net (code "23") (name "Net-(U$5-P-G)") (class "Default")
      (node (ref "R6") (pin "2") (pinfunction "2_2") (pintype "passive"))
      (node (ref "R7") (pin "2") (pinfunction "2_2") (pintype "passive"))
      (node (ref "U$5") (pin "GND") (pinfunction "P-G_GND") (pintype "passive"))
    )
    (net (code "24") (name "Net-(U$6-P-D)") (class "Default")
      (node (ref "D6") (pin "A") (pinfunction "A_A") (pintype "passive"))
      (node (ref "MOTOR4") (pin "V-") (pinfunction "V-_V-") (pintype "bidirectional"))
      (node (ref "U$6") (pin "DRN") (pinfunction "P-D_DRN") (pintype "passive"))
    )
    (net (code "25") (name "Net-(U$6-P-G)") (class "Default")
      (node (ref "R8") (pin "2") (pinfunction "2_2") (pintype "passive"))
      (node (ref "R9") (pin "2") (pinfunction "2_2") (pintype "passive"))
      (node (ref "U$6") (pin "GND") (pinfunction "P-G_GND") (pintype "passive"))
    )
    (net (code "26") (name "Net-(U$7-P-D)") (class "Default")
      (node (ref "D5") (pin "A") (pinfunction "A_A") (pintype "passive"))
      (node (ref "MOTOR3") (pin "V-") (pinfunction "V-_V-") (pintype "bidirectional"))
      (node (ref "U$7") (pin "DRN") (pinfunction "P-D_DRN") (pintype "passive"))
    )
    (net (code "27") (name "Net-(U$7-P-G)") (class "Default")
      (node (ref "R10") (pin "2") (pinfunction "2_2") (pintype "passive"))
      (node (ref "R11") (pin "2") (pinfunction "2_2") (pintype "passive"))
      (node (ref "U$7") (pin "GND") (pinfunction "P-G_GND") (pintype "passive"))
    )
    (net (code "28") (name "Net-(U1-AVDD)") (class "Default")
      (node (ref "C8") (pin "1") (pinfunction "1_1") (pintype "passive"))
      (node (ref "U1") (pin "60") (pinfunction "AVDD_60") (pintype "bidirectional"))
    )
    (net (code "29") (name "Net-(U1-PB4(OC2A{slash}PCINT4))") (class "Default")
      (node (ref "R14") (pin "2") (pinfunction "2_2") (pintype "passive"))
      (node (ref "U1") (pin "40") (pinfunction "PB4(OC2A/PCINT4)_40") (pintype "bidirectional"))
    )
    (net (code "30") (name "Net-(U1-PB6(OC1B{slash}PCINT6))") (class "Default")
      (node (ref "R4") (pin "2") (pinfunction "2_2") (pintype "passive"))
      (node (ref "U1") (pin "42") (pinfunction "PB6(OC1B/PCINT6)_42") (pintype "bidirectional"))
    )
    (net (code "31") (name "Net-(U1-PB7(OC0A{slash}OC1C{slash}PCINT7))") (class "Default")
      (node (ref "R3") (pin "2") (pinfunction "2_2") (pintype "passive"))
      (node (ref "U1") (pin "43") (pinfunction "PB7(OC0A/OC1C/PCINT7)_43") (pintype "bidirectional"))
    )
    (net (code "32") (name "Net-(U1-XTAL1)") (class "Default")
      (node (ref "C6") (pin "1") (pinfunction "1_1") (pintype "passive"))
      (node (ref "U1") (pin "57") (pinfunction "XTAL1_57") (pintype "bidirectional"))
      (node (ref "Y2") (pin "1") (pinfunction "1_1") (pintype "passive"))
    )
    (net (code "33") (name "Net-(U1-XTAL2)") (class "Default")
      (node (ref "C5") (pin "1") (pinfunction "1_1") (pintype "passive"))
      (node (ref "U1") (pin "56") (pinfunction "XTAL2_56") (pintype "bidirectional"))
      (node (ref "Y2") (pin "3") (pinfunction "2_3") (pintype "passive"))
    )
    (net (code "34") (name "PB5") (class "Default")
      (node (ref "C15") (pin "1") (pinfunction "1_1") (pintype "passive"))
      (node (ref "J2") (pin "8") (pinfunction "8_8") (pintype "passive"))
      (node (ref "R6") (pin "1") (pinfunction "1_1") (pintype "passive"))
      (node (ref "U1") (pin "41") (pinfunction "PB5(OC1A/PCINT5)_41") (pintype "bidirectional"))
    )
    (net (code "35") (name "PE3") (class "Default")
      (node (ref "C1") (pin "1") (pinfunction "1_1") (pintype "passive"))
      (node (ref "J2") (pin "5") (pinfunction "5_5") (pintype "passive"))
      (node (ref "R1") (pin "1") (pinfunction "1_1") (pintype "passive"))
      (node (ref "U1") (pin "49") (pinfunction "PE3(OC3A/AIN1)_49") (pintype "bidirectional"))
    )
    (net (code "36") (name "PE4") (class "Default")
      (node (ref "C19") (pin "1") (pinfunction "1_1") (pintype "passive"))
      (node (ref "J2") (pin "6") (pinfunction "6_6") (pintype "passive"))
      (node (ref "R10") (pin "1") (pinfunction "1_1") (pintype "passive"))
      (node (ref "U1") (pin "50") (pinfunction "PE4(OC3B/INT4)_50") (pintype "bidirectional"))
    )
    (net (code "37") (name "PE5") (class "Default")
      (node (ref "C17") (pin "1") (pinfunction "1_1") (pintype "passive"))
      (node (ref "J2") (pin "7") (pinfunction "7_7") (pintype "passive"))
      (node (ref "R8") (pin "1") (pinfunction "1_1") (pintype "passive"))
      (node (ref "U1") (pin "51") (pinfunction "PE5(OC3C/INT5)_51") (pintype "bidirectional"))
    )
    (net (code "38") (name "RESET") (class "Default")
      (node (ref "C13") (pin "2") (pinfunction "2_2") (pintype "passive"))
      (node (ref "J1") (pin "5") (pinfunction "5_5") (pintype "passive"))
      (node (ref "R5") (pin "1") (pinfunction "1_1") (pintype "passive"))
      (node (ref "SW1") (pin "1") (pinfunction "1_1") (pintype "passive"))
      (node (ref "SW1") (pin "2") (pinfunction "1_2") (pintype "passive"))
      (node (ref "U1") (pin "12") (pinfunction "RSTN_12") (pintype "bidirectional"))
    )
    (net (code "39") (name "RX0") (class "Default")
      (node (ref "JP1") (pin "TXO") (pinfunction "3_TXO") (pintype "passive"))
      (node (ref "U1") (pin "46") (pinfunction "PE0(RXD0/PCINT8)_46") (pintype "bidirectional"))
    )
    (net (code "40") (name "RX1") (class "Default")
      (node (ref "JP2") (pin "TXO") (pinfunction "3_TXO") (pintype "passive"))
      (node (ref "U1") (pin "27") (pinfunction "PD2(RXD1/INT2)_27") (pintype "bidirectional"))
    )
    (net (code "41") (name "SCK") (class "Default")
      (node (ref "J1") (pin "3") (pinfunction "3_3") (pintype "passive"))
      (node (ref "U1") (pin "37") (pinfunction "PB1(SCK/PCINT1)_37") (pintype "bidirectional"))
    )
    (net (code "42") (name "SCL") (class "Default")
      (node (ref "J2") (pin "10") (pinfunction "10_10") (pintype "passive"))
      (node (ref "R13") (pin "1") (pinfunction "1_1") (pintype "passive"))
      (node (ref "U$8") (pin "SCL/SPC") (pinfunction "SCL/SPC_SCL/SPC") (pintype "bidirectional"))
      (node (ref "U1") (pin "25") (pinfunction "PD0(SCL/INT0)_25") (pintype "bidirectional"))
    )
    (net (code "43") (name "SDA") (class "Default")
      (node (ref "J2") (pin "9") (pinfunction "9_9") (pintype "passive"))
      (node (ref "R12") (pin "1") (pinfunction "1_1") (pintype "passive"))
      (node (ref "U$8") (pin "SDA/SDI/SDO") (pinfunction "SDA/SDI/SDO_SDA/SDI/SDO") (pintype "bidirectional"))
      (node (ref "U1") (pin "26") (pinfunction "PD1(SDA/INT1)_26") (pintype "bidirectional"))
    )
    (net (code "44") (name "TX0") (class "Default")
      (node (ref "JP1") (pin "RXI") (pinfunction "2_RXI") (pintype "passive"))
      (node (ref "U1") (pin "47") (pinfunction "PE1(TXD0)_47") (pintype "bidirectional"))
    )
    (net (code "45") (name "TX1") (class "Default")
      (node (ref "JP2") (pin "RXI") (pinfunction "2_RXI") (pintype "passive"))
      (node (ref "U1") (pin "28") (pinfunction "PD3(TXD1/INT3)_28") (pintype "bidirectional"))
    )
    (net (code "46") (name "VBAT") (class "Default")
      (node (ref "C16") (pin "1") (pinfunction "+_1") (pintype "passive"))
      (node (ref "C18") (pin "1") (pinfunction "+_1") (pintype "passive"))
      (node (ref "C2") (pin "1") (pinfunction "1_1") (pintype "passive"))
      (node (ref "C20") (pin "1") (pinfunction "+_1") (pintype "passive"))
      (node (ref "C4") (pin "1") (pinfunction "+_1") (pintype "passive"))
      (node (ref "D1") (pin "C") (pinfunction "C_C") (pintype "passive"))
      (node (ref "D4") (pin "C") (pinfunction "C_C") (pintype "passive"))
      (node (ref "D5") (pin "C") (pinfunction "C_C") (pintype "passive"))
      (node (ref "D6") (pin "C") (pinfunction "C_C") (pintype "passive"))
      (node (ref "J2") (pin "3") (pinfunction "3_3") (pintype "passive"))
      (node (ref "J3") (pin "2") (pinfunction "2_2") (pintype "passive"))
      (node (ref "MOTOR1") (pin "V+") (pinfunction "V+_V+") (pintype "bidirectional"))
      (node (ref "MOTOR2") (pin "V+") (pinfunction "V+_V+") (pintype "bidirectional"))
      (node (ref "MOTOR3") (pin "V+") (pinfunction "V+_V+") (pintype "bidirectional"))
      (node (ref "MOTOR4") (pin "V+") (pinfunction "V+_V+") (pintype "bidirectional"))
      (node (ref "U$4") (pin "1") (pinfunction "IN_1") (pintype "input"))
      (node (ref "U$4") (pin "3") (pinfunction "EN_3") (pintype "input"))
    )
    (net (code "47") (name "unconnected-(J1-Pad2)") (class "Default")
      (node (ref "J1") (pin "2") (pinfunction "2_2") (pintype "passive"))
    )
    (net (code "48") (name "unconnected-(JP1-4-PadVCC)") (class "Default")
      (node (ref "JP1") (pin "VCC") (pinfunction "4_VCC") (pintype "passive"))
    )
    (net (code "49") (name "unconnected-(JP1-5-PadCTS)") (class "Default")
      (node (ref "JP1") (pin "CTS") (pinfunction "5_CTS") (pintype "passive"))
    )
    (net (code "50") (name "unconnected-(JP2-1-PadDTR)") (class "Default")
      (node (ref "JP2") (pin "DTR") (pinfunction "1_DTR") (pintype "passive"))
    )
    (net (code "51") (name "unconnected-(JP2-4-PadVCC)") (class "Default")
      (node (ref "JP2") (pin "VCC") (pinfunction "4_VCC") (pintype "passive"))
    )
    (net (code "52") (name "unconnected-(JP2-5-PadCTS)") (class "Default")
      (node (ref "JP2") (pin "CTS") (pinfunction "5_CTS") (pintype "passive"))
    )
    (net (code "53") (name "unconnected-(U$8-PadDRDY_M)") (class "Default")
      (node (ref "U$8") (pin "DRDY_M") (pinfunction "DRDY_M_DRDY_M") (pintype "bidirectional"))
    )
    (net (code "54") (name "unconnected-(U$8-PadINT1_A{slash}G)") (class "Default")
      (node (ref "U$8") (pin "INT1_A/G") (pinfunction "INT1_A/G_INT1_A/G") (pintype "bidirectional"))
    )
    (net (code "55") (name "unconnected-(U$8-PadINT2_A{slash}G)") (class "Default")
      (node (ref "U$8") (pin "INT2_A/G") (pinfunction "INT2_A/G_INT2_A/G") (pintype "bidirectional"))
    )
    (net (code "56") (name "unconnected-(U$8-PadINT_M)") (class "Default")
      (node (ref "U$8") (pin "INT_M") (pinfunction "INT_M_INT_M") (pintype "bidirectional"))
    )
    (net (code "57") (name "unconnected-(U1-AREF-Pad62)") (class "Default")
      (node (ref "U1") (pin "62") (pinfunction "AREF_62") (pintype "bidirectional"))
    )
    (net (code "58") (name "unconnected-(U1-PB0(SSN{slash}PCINT0)-Pad36)") (class "Default")
      (node (ref "U1") (pin "36") (pinfunction "PB0(SSN/PCINT0)_36") (pintype "bidirectional"))
    )
    (net (code "59") (name "unconnected-(U1-PD4(ICP1)-Pad29)") (class "Default")
      (node (ref "U1") (pin "29") (pinfunction "PD4(ICP1)_29") (pintype "bidirectional"))
    )
    (net (code "60") (name "unconnected-(U1-PD5(XCK1)-Pad30)") (class "Default")
      (node (ref "U1") (pin "30") (pinfunction "PD5(XCK1)_30") (pintype "bidirectional"))
    )
    (net (code "61") (name "unconnected-(U1-PD6(T1)-Pad31)") (class "Default")
      (node (ref "U1") (pin "31") (pinfunction "PD6(T1)_31") (pintype "bidirectional"))
    )
    (net (code "62") (name "unconnected-(U1-PD7(T0)-Pad32)") (class "Default")
      (node (ref "U1") (pin "32") (pinfunction "PD7(T0)_32") (pintype "bidirectional"))
    )
    (net (code "63") (name "unconnected-(U1-PE2(XCK0{slash}AIN0)-Pad48)") (class "Default")
      (node (ref "U1") (pin "48") (pinfunction "PE2(XCK0/AIN0)_48") (pintype "bidirectional"))
    )
    (net (code "64") (name "unconnected-(U1-PE6(T3{slash}INT6)-Pad52)") (class "Default")
      (node (ref "U1") (pin "52") (pinfunction "PE6(T3/INT6)_52") (pintype "bidirectional"))
    )
    (net (code "65") (name "unconnected-(U1-PE7(ICP3{slash}INT7{slash}CLKO)-Pad53)") (class "Default")
      (node (ref "U1") (pin "53") (pinfunction "PE7(ICP3/INT7/CLKO)_53") (pintype "bidirectional"))
    )
    (net (code "66") (name "unconnected-(U1-PF0(ADC0)-Pad63)") (class "Default")
      (node (ref "U1") (pin "63") (pinfunction "PF0(ADC0)_63") (pintype "bidirectional"))
    )
    (net (code "67") (name "unconnected-(U1-PF1(ADC1)-Pad64)") (class "Default")
      (node (ref "U1") (pin "64") (pinfunction "PF1(ADC1)_64") (pintype "bidirectional"))
    )
    (net (code "68") (name "unconnected-(U1-PF2(ADC2{slash}DIG2)-Pad1)") (class "Default")
      (node (ref "U1") (pin "1") (pinfunction "PF2(ADC2/DIG2)_1") (pintype "bidirectional"))
    )
    (net (code "69") (name "unconnected-(U1-PF3(ADC3{slash}DIG4)-Pad2)") (class "Default")
      (node (ref "U1") (pin "2") (pinfunction "PF3(ADC3/DIG4)_2") (pintype "bidirectional"))
    )
    (net (code "70") (name "unconnected-(U1-PF4(ADC4{slash}TCK)-Pad3)") (class "Default")
      (node (ref "U1") (pin "3") (pinfunction "PF4(ADC4/TCK)_3") (pintype "bidirectional"))
    )
    (net (code "71") (name "unconnected-(U1-PF5(ADC5{slash}TMS)-Pad4)") (class "Default")
      (node (ref "U1") (pin "4") (pinfunction "PF5(ADC5/TMS)_4") (pintype "bidirectional"))
    )
    (net (code "72") (name "unconnected-(U1-PF6(ADC6{slash}TDO)-Pad5)") (class "Default")
      (node (ref "U1") (pin "5") (pinfunction "PF6(ADC6/TDO)_5") (pintype "bidirectional"))
    )
    (net (code "73") (name "unconnected-(U1-PF7(ADC7{slash}TDI)-Pad6)") (class "Default")
      (node (ref "U1") (pin "6") (pinfunction "PF7(ADC7/TDI)_6") (pintype "bidirectional"))
    )
    (net (code "74") (name "unconnected-(U1-PG0(DIG3)-Pad14)") (class "Default")
      (node (ref "U1") (pin "14") (pinfunction "PG0(DIG3)_14") (pintype "bidirectional"))
    )
    (net (code "75") (name "unconnected-(U1-PG1(DIG1)-Pad15)") (class "Default")
      (node (ref "U1") (pin "15") (pinfunction "PG1(DIG1)_15") (pintype "bidirectional"))
    )
    (net (code "76") (name "unconnected-(U1-PG2(AMR)-Pad16)") (class "Default")
      (node (ref "U1") (pin "16") (pinfunction "PG2(AMR)_16") (pintype "bidirectional"))
    )
    (net (code "77") (name "unconnected-(U1-PG3(TOSC2)-Pad17)") (class "Default")
      (node (ref "U1") (pin "17") (pinfunction "PG3(TOSC2)_17") (pintype "bidirectional"))
    )
    (net (code "78") (name "unconnected-(U1-PG4(TOSC1)-Pad18)") (class "Default")
      (node (ref "U1") (pin "18") (pinfunction "PG4(TOSC1)_18") (pintype "bidirectional"))
    )
    (net (code "79") (name "unconnected-(U1-PG5(OC0B)-Pad19)") (class "Default")
      (node (ref "U1") (pin "19") (pinfunction "PG5(OC0B)_19") (pintype "bidirectional"))
    )
    (net (code "80") (name "unconnected-(U1-RSTON-Pad13)") (class "Default")
      (node (ref "U1") (pin "13") (pinfunction "RSTON_13") (pintype "bidirectional"))
    )
  )
)
